# ignition6.net
KiCad netlist of a schematic drawn in EAGLE
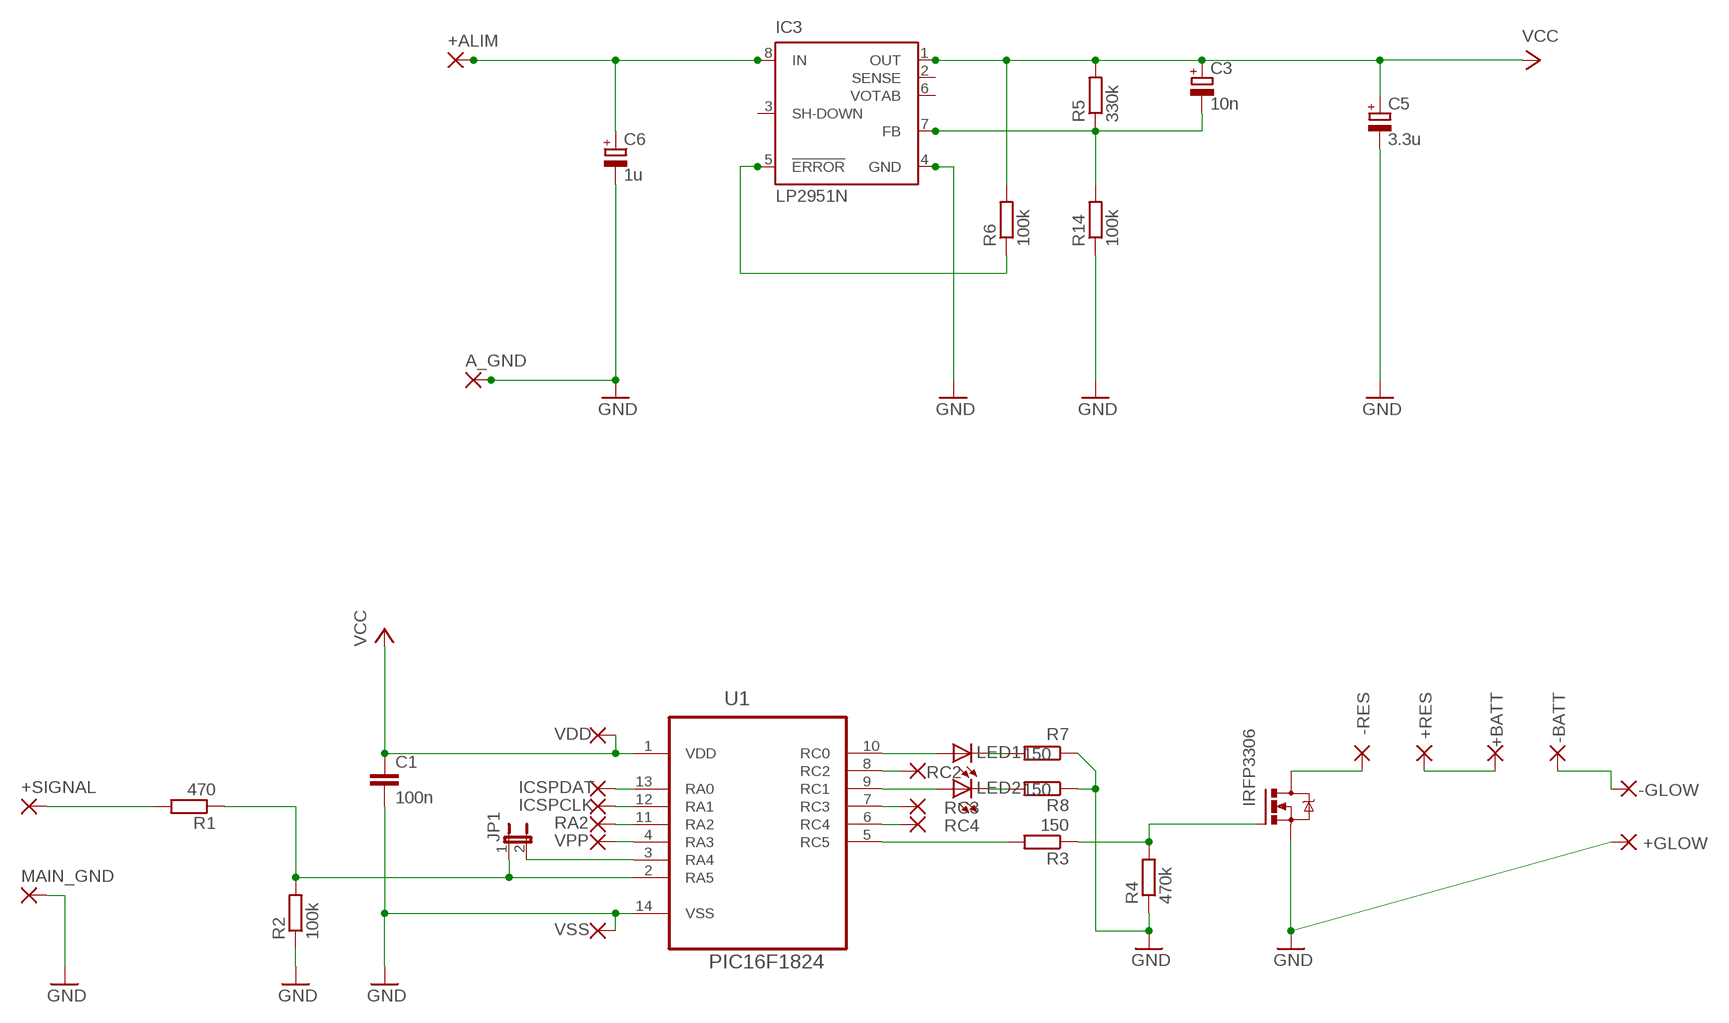
[diagram p0: schematic, sheet 1]

(export (version "E")
  (design (tool "Eeschema 10.0.6"))
  (components
    (comp (ref "+ALIM")
      (value "2,15/1,0")
      (footprint "eagle-import:2,15_1,0")
      (libsource (lib "eagle-import") (part "2,15/1,0"))
    )
    (comp (ref "+BATT")
      (value "WIREPAD3,17/1,3")
      (footprint "eagle-import:3,17_1,3")
      (libsource (lib "eagle-import") (part "WIREPAD3,17/1,3"))
    )
    (comp (ref "+GLOW")
      (value "WIREPAD3,17/1,3")
      (footprint "eagle-import:3,17_1,3")
      (libsource (lib "eagle-import") (part "WIREPAD3,17/1,3"))
    )
    (comp (ref "+RES")
      (value "WIREPAD3,17/1,3")
      (footprint "eagle-import:3,17_1,3")
      (libsource (lib "eagle-import") (part "WIREPAD3,17/1,3"))
    )
    (comp (ref "+SIGNAL")
      (value "2,15/1,0")
      (footprint "eagle-import:2,15_1,0")
      (libsource (lib "eagle-import") (part "2,15/1,0"))
    )
    (comp (ref "-BATT")
      (value "WIREPAD3,17/1,3")
      (footprint "eagle-import:3,17_1,3")
      (libsource (lib "eagle-import") (part "WIREPAD3,17/1,3"))
    )
    (comp (ref "-GLOW")
      (value "WIREPAD3,17/1,3")
      (footprint "eagle-import:3,17_1,3")
      (libsource (lib "eagle-import") (part "WIREPAD3,17/1,3"))
    )
    (comp (ref "-RES")
      (value "WIREPAD3,17/1,3")
      (footprint "eagle-import:3,17_1,3")
      (libsource (lib "eagle-import") (part "WIREPAD3,17/1,3"))
    )
    (comp (ref "A_GND")
      (value "2,15/1,0")
      (footprint "eagle-import:2,15_1,0")
      (libsource (lib "eagle-import") (part "2,15/1,0"))
    )
    (comp (ref "C1")
      (value "100n")
      (footprint "eagle-import:C050-035X075")
      (libsource (lib "eagle-import") (part "C-EU050-035X075"))
    )
    (comp (ref "C3")
      (value "10n")
      (footprint "eagle-import:E5-6")
      (libsource (lib "eagle-import") (part "CPOL-EUE5-6"))
    )
    (comp (ref "C5")
      (value "3.3u")
      (footprint "eagle-import:E2,5-5")
      (libsource (lib "eagle-import") (part "CPOL-EUE2.5-5"))
    )
    (comp (ref "C6")
      (value "1u")
      (footprint "eagle-import:E2,5-5")
      (libsource (lib "eagle-import") (part "CPOL-EUE2.5-5"))
    )
    (comp (ref "IC3")
      (value "LP2951N")
      (footprint "eagle-import:DIL08")
      (libsource (lib "eagle-import") (part "LP2951N"))
    )
    (comp (ref "ICSPCLK")
      (value "2,15/1,0")
      (footprint "eagle-import:2,15_1,0")
      (libsource (lib "eagle-import") (part "2,15/1,0"))
    )
    (comp (ref "ICSPDAT")
      (value "2,15/1,0")
      (footprint "eagle-import:2,15_1,0")
      (libsource (lib "eagle-import") (part "2,15/1,0"))
    )
    (comp (ref "JP1")
      (value "JP1E")
      (footprint "eagle-import:JP1")
      (libsource (lib "eagle-import") (part "JP1E"))
    )
    (comp (ref "LED1")
      (value "LED3MM")
      (footprint "eagle-import:LED3MM")
      (libsource (lib "eagle-import") (part "LED3MM"))
    )
    (comp (ref "LED2")
      (value "LED3MM")
      (footprint "eagle-import:LED3MM")
      (libsource (lib "eagle-import") (part "LED3MM"))
    )
    (comp (ref "MAIN_GND")
      (value "2,15/1,0")
      (footprint "eagle-import:2,15_1,0")
      (libsource (lib "eagle-import") (part "2,15/1,0"))
    )
    (comp (ref "Q2")
      (value "IRFP3306")
      (footprint "eagle-import:TO247BV")
      (libsource (lib "eagle-import") (part "IRFPC40"))
    )
    (comp (ref "R1")
      (value "470")
      (footprint "eagle-import:0207_7")
      (libsource (lib "eagle-import") (part "R-EU_0207/7"))
    )
    (comp (ref "R2")
      (value "100k")
      (footprint "eagle-import:0207_7")
      (libsource (lib "eagle-import") (part "R-EU_0207/7"))
    )
    (comp (ref "R3")
      (value "150")
      (footprint "eagle-import:0207_7")
      (libsource (lib "eagle-import") (part "R-EU_0207/7"))
    )
    (comp (ref "R4")
      (value "470k")
      (footprint "eagle-import:0207_7")
      (libsource (lib "eagle-import") (part "R-EU_0207/7"))
    )
    (comp (ref "R5")
      (value "330k")
      (footprint "eagle-import:0207_7")
      (libsource (lib "eagle-import") (part "R-EU_0207/7"))
    )
    (comp (ref "R6")
      (value "100k")
      (footprint "eagle-import:0207_7")
      (libsource (lib "eagle-import") (part "R-EU_0207/7"))
    )
    (comp (ref "R7")
      (value "150")
      (footprint "eagle-import:0207_7")
      (libsource (lib "eagle-import") (part "R-EU_0207/7"))
    )
    (comp (ref "R8")
      (value "150")
      (footprint "eagle-import:0207_7")
      (libsource (lib "eagle-import") (part "R-EU_0207/7"))
    )
    (comp (ref "R14")
      (value "100k")
      (footprint "eagle-import:0207_7")
      (libsource (lib "eagle-import") (part "R-EU_0207/7"))
    )
    (comp (ref "RA2")
      (value "2,15/1,0")
      (footprint "eagle-import:2,15_1,0")
      (libsource (lib "eagle-import") (part "2,15/1,0"))
    )
    (comp (ref "RC2")
      (value "2,15/1,0")
      (footprint "eagle-import:2,15_1,0")
      (libsource (lib "eagle-import") (part "2,15/1,0"))
    )
    (comp (ref "RC3")
      (value "2,15/1,0")
      (footprint "eagle-import:2,15_1,0")
      (libsource (lib "eagle-import") (part "2,15/1,0"))
    )
    (comp (ref "RC4")
      (value "2,15/1,0")
      (footprint "eagle-import:2,15_1,0")
      (libsource (lib "eagle-import") (part "2,15/1,0"))
    )
    (comp (ref "U1")
      (value "PIC16F1824")
      (footprint "eagle-import:DIP254P762X533-14")
      (fields (field (name "MPN") "PIC16F1824-I/P"))
      (libsource (lib "eagle-import") (part "PIC16F1824-I/P"))
    )
    (comp (ref "VDD")
      (value "WIREPAD2,15/1,0")
      (footprint "eagle-import:2,15_1,0")
      (libsource (lib "eagle-import") (part "WIREPAD2,15/1,0"))
    )
    (comp (ref "VPP")
      (value "2,15/1,0")
      (footprint "eagle-import:2,15_1,0")
      (libsource (lib "eagle-import") (part "2,15/1,0"))
    )
    (comp (ref "VSS")
      (value "WIREPAD2,15/1,0")
      (footprint "eagle-import:2,15_1,0")
      (libsource (lib "eagle-import") (part "WIREPAD2,15/1,0"))
    )
  )
  (nets
    (net (code "1") (name "GND") (class "Default")
      (node (ref "+GLOW") (pin "1") (pinfunction "P_1") (pintype "passive"))
      (node (ref "A_GND") (pin "1") (pinfunction "P_1") (pintype "passive"))
      (node (ref "C1") (pin "2") (pinfunction "2_2") (pintype "passive"))
      (node (ref "C5") (pin "-") (pinfunction "-_-") (pintype "passive"))
      (node (ref "C6") (pin "-") (pinfunction "-_-") (pintype "passive"))
      (node (ref "IC3") (pin "4") (pinfunction "GND_4") (pintype "power_in"))
      (node (ref "MAIN_GND") (pin "1") (pinfunction "P_1") (pintype "passive"))
      (node (ref "Q2") (pin "S") (pinfunction "S_S") (pintype "passive"))
      (node (ref "R14") (pin "1") (pinfunction "1_1") (pintype "passive"))
      (node (ref "R2") (pin "1") (pinfunction "1_1") (pintype "passive"))
      (node (ref "R4") (pin "1") (pinfunction "1_1") (pintype "passive"))
      (node (ref "R7") (pin "1") (pinfunction "1_1") (pintype "passive"))
      (node (ref "R8") (pin "1") (pinfunction "1_1") (pintype "passive"))
      (node (ref "U1") (pin "14") (pinfunction "VSS_14") (pintype "power_in"))
      (node (ref "VSS") (pin "1") (pinfunction "P_1") (pintype "passive"))
    )
    (net (code "2") (name "Net-(+ALIM-P)") (class "Default")
      (node (ref "+ALIM") (pin "1") (pinfunction "P_1") (pintype "passive"))
      (node (ref "C6") (pin "+") (pinfunction "+_+") (pintype "passive"))
      (node (ref "IC3") (pin "8") (pinfunction "IN_8") (pintype "input"))
    )
    (net (code "3") (name "Net-(+BATT-P)") (class "Default")
      (node (ref "+BATT") (pin "1") (pinfunction "P_1") (pintype "passive"))
      (node (ref "+RES") (pin "1") (pinfunction "P_1") (pintype "passive"))
    )
    (net (code "4") (name "Net-(+SIGNAL-P)") (class "Default")
      (node (ref "+SIGNAL") (pin "1") (pinfunction "P_1") (pintype "passive"))
      (node (ref "R1") (pin "2") (pinfunction "2_2") (pintype "passive"))
    )
    (net (code "5") (name "Net-(-BATT-P)") (class "Default")
      (node (ref "-BATT") (pin "1") (pinfunction "P_1") (pintype "passive"))
      (node (ref "-GLOW") (pin "1") (pinfunction "P_1") (pintype "passive"))
    )
    (net (code "6") (name "Net-(-RES-P)") (class "Default")
      (node (ref "-RES") (pin "1") (pinfunction "P_1") (pintype "passive"))
      (node (ref "Q2") (pin "D") (pinfunction "D_D") (pintype "passive"))
    )
    (net (code "7") (name "Net-(IC3-FB)") (class "Default")
      (node (ref "C3") (pin "-") (pinfunction "-_-") (pintype "passive"))
      (node (ref "IC3") (pin "7") (pinfunction "FB_7") (pintype "input"))
      (node (ref "R14") (pin "2") (pinfunction "2_2") (pintype "passive"))
      (node (ref "R5") (pin "1") (pinfunction "1_1") (pintype "passive"))
    )
    (net (code "8") (name "Net-(IC3-~{ERROR})") (class "Default")
      (node (ref "IC3") (pin "5") (pinfunction "~{ERROR}_5") (pintype "output"))
      (node (ref "R6") (pin "1") (pinfunction "1_1") (pintype "passive"))
    )
    (net (code "9") (name "Net-(ICSPCLK-P)") (class "Default")
      (node (ref "ICSPCLK") (pin "1") (pinfunction "P_1") (pintype "passive"))
      (node (ref "U1") (pin "12") (pinfunction "RA1_12") (pintype "bidirectional"))
    )
    (net (code "10") (name "Net-(ICSPDAT-P)") (class "Default")
      (node (ref "ICSPDAT") (pin "1") (pinfunction "P_1") (pintype "passive"))
      (node (ref "U1") (pin "13") (pinfunction "RA0_13") (pintype "bidirectional"))
    )
    (net (code "11") (name "Net-(LED1-C)") (class "Default")
      (node (ref "LED1") (pin "K") (pinfunction "C_K") (pintype "passive"))
      (node (ref "R7") (pin "2") (pinfunction "2_2") (pintype "passive"))
    )
    (net (code "12") (name "Net-(LED2-C)") (class "Default")
      (node (ref "LED2") (pin "K") (pinfunction "C_K") (pintype "passive"))
      (node (ref "R8") (pin "2") (pinfunction "2_2") (pintype "passive"))
    )
    (net (code "13") (name "Net-(Q2-PadG)") (class "Default")
      (node (ref "Q2") (pin "G") (pinfunction "G_G") (pintype "passive"))
      (node (ref "R3") (pin "1") (pinfunction "1_1") (pintype "passive"))
      (node (ref "R4") (pin "2") (pinfunction "2_2") (pintype "passive"))
    )
    (net (code "14") (name "Net-(RA2-P)") (class "Default")
      (node (ref "RA2") (pin "1") (pinfunction "P_1") (pintype "passive"))
      (node (ref "U1") (pin "11") (pinfunction "RA2_11") (pintype "bidirectional"))
    )
    (net (code "15") (name "Net-(RC2-P)") (class "Default")
      (node (ref "RC2") (pin "1") (pinfunction "P_1") (pintype "passive"))
      (node (ref "U1") (pin "8") (pinfunction "RC2_8") (pintype "bidirectional"))
    )
    (net (code "16") (name "Net-(RC3-P)") (class "Default")
      (node (ref "RC3") (pin "1") (pinfunction "P_1") (pintype "passive"))
      (node (ref "U1") (pin "7") (pinfunction "RC3_7") (pintype "bidirectional"))
    )
    (net (code "17") (name "Net-(RC4-P)") (class "Default")
      (node (ref "RC4") (pin "1") (pinfunction "P_1") (pintype "passive"))
      (node (ref "U1") (pin "6") (pinfunction "RC4_6") (pintype "bidirectional"))
    )
    (net (code "18") (name "Net-(U1-RA3)") (class "Default")
      (node (ref "U1") (pin "4") (pinfunction "RA3_4") (pintype "input"))
      (node (ref "VPP") (pin "1") (pinfunction "P_1") (pintype "passive"))
    )
    (net (code "19") (name "Net-(U1-RA4)") (class "Default")
      (node (ref "JP1") (pin "2") (pinfunction "2_2") (pintype "passive"))
      (node (ref "U1") (pin "3") (pinfunction "RA4_3") (pintype "bidirectional"))
    )
    (net (code "20") (name "Net-(U1-RA5)") (class "Default")
      (node (ref "JP1") (pin "1") (pinfunction "1_1") (pintype "passive"))
      (node (ref "R1") (pin "1") (pinfunction "1_1") (pintype "passive"))
      (node (ref "R2") (pin "2") (pinfunction "2_2") (pintype "passive"))
      (node (ref "U1") (pin "2") (pinfunction "RA5_2") (pintype "bidirectional"))
    )
    (net (code "21") (name "Net-(U1-RC0)") (class "Default")
      (node (ref "LED1") (pin "A") (pinfunction "A_A") (pintype "passive"))
      (node (ref "U1") (pin "10") (pinfunction "RC0_10") (pintype "bidirectional"))
    )
    (net (code "22") (name "Net-(U1-RC1)") (class "Default")
      (node (ref "LED2") (pin "A") (pinfunction "A_A") (pintype "passive"))
      (node (ref "U1") (pin "9") (pinfunction "RC1_9") (pintype "bidirectional"))
    )
    (net (code "23") (name "Net-(U1-RC5)") (class "Default")
      (node (ref "R3") (pin "2") (pinfunction "2_2") (pintype "passive"))
      (node (ref "U1") (pin "5") (pinfunction "RC5_5") (pintype "bidirectional"))
    )
    (net (code "24") (name "VCC") (class "Default")
      (node (ref "C1") (pin "1") (pinfunction "1_1") (pintype "passive"))
      (node (ref "C3") (pin "+") (pinfunction "+_+") (pintype "passive"))
      (node (ref "C5") (pin "+") (pinfunction "+_+") (pintype "passive"))
      (node (ref "IC3") (pin "1") (pinfunction "OUT_1") (pintype "input"))
      (node (ref "R5") (pin "2") (pinfunction "2_2") (pintype "passive"))
      (node (ref "R6") (pin "2") (pinfunction "2_2") (pintype "passive"))
      (node (ref "U1") (pin "1") (pinfunction "VDD_1") (pintype "power_in"))
      (node (ref "VDD") (pin "1") (pinfunction "P_1") (pintype "passive"))
    )
    (net (code "25") (name "unconnected-(IC3-SENSE-Pad2)") (class "Default")
      (node (ref "IC3") (pin "2") (pinfunction "SENSE_2") (pintype "input"))
    )
    (net (code "26") (name "unconnected-(IC3-SH-DOWN-Pad3)") (class "Default")
      (node (ref "IC3") (pin "3") (pinfunction "SH-DOWN_3") (pintype "input"))
    )
    (net (code "27") (name "unconnected-(IC3-VOTAB-Pad6)") (class "Default")
      (node (ref "IC3") (pin "6") (pinfunction "VOTAB_6") (pintype "passive"))
    )
  )
)
